# ComputeModule.net
KiCad netlist of a schematic drawn in Altium Designer
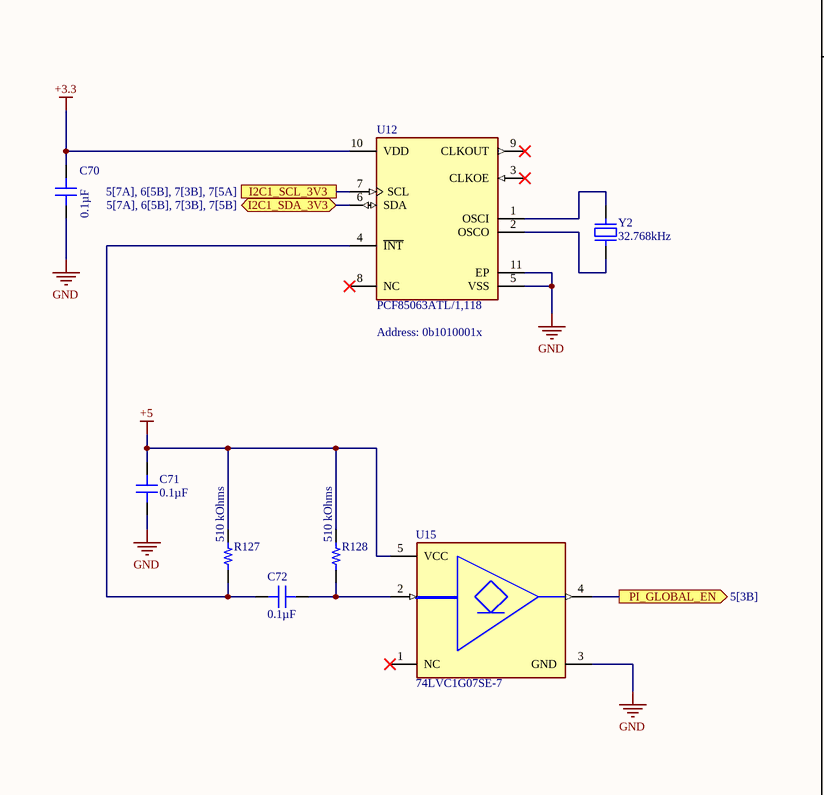
[diagram p0: ComputeModule.SchDoc, left]
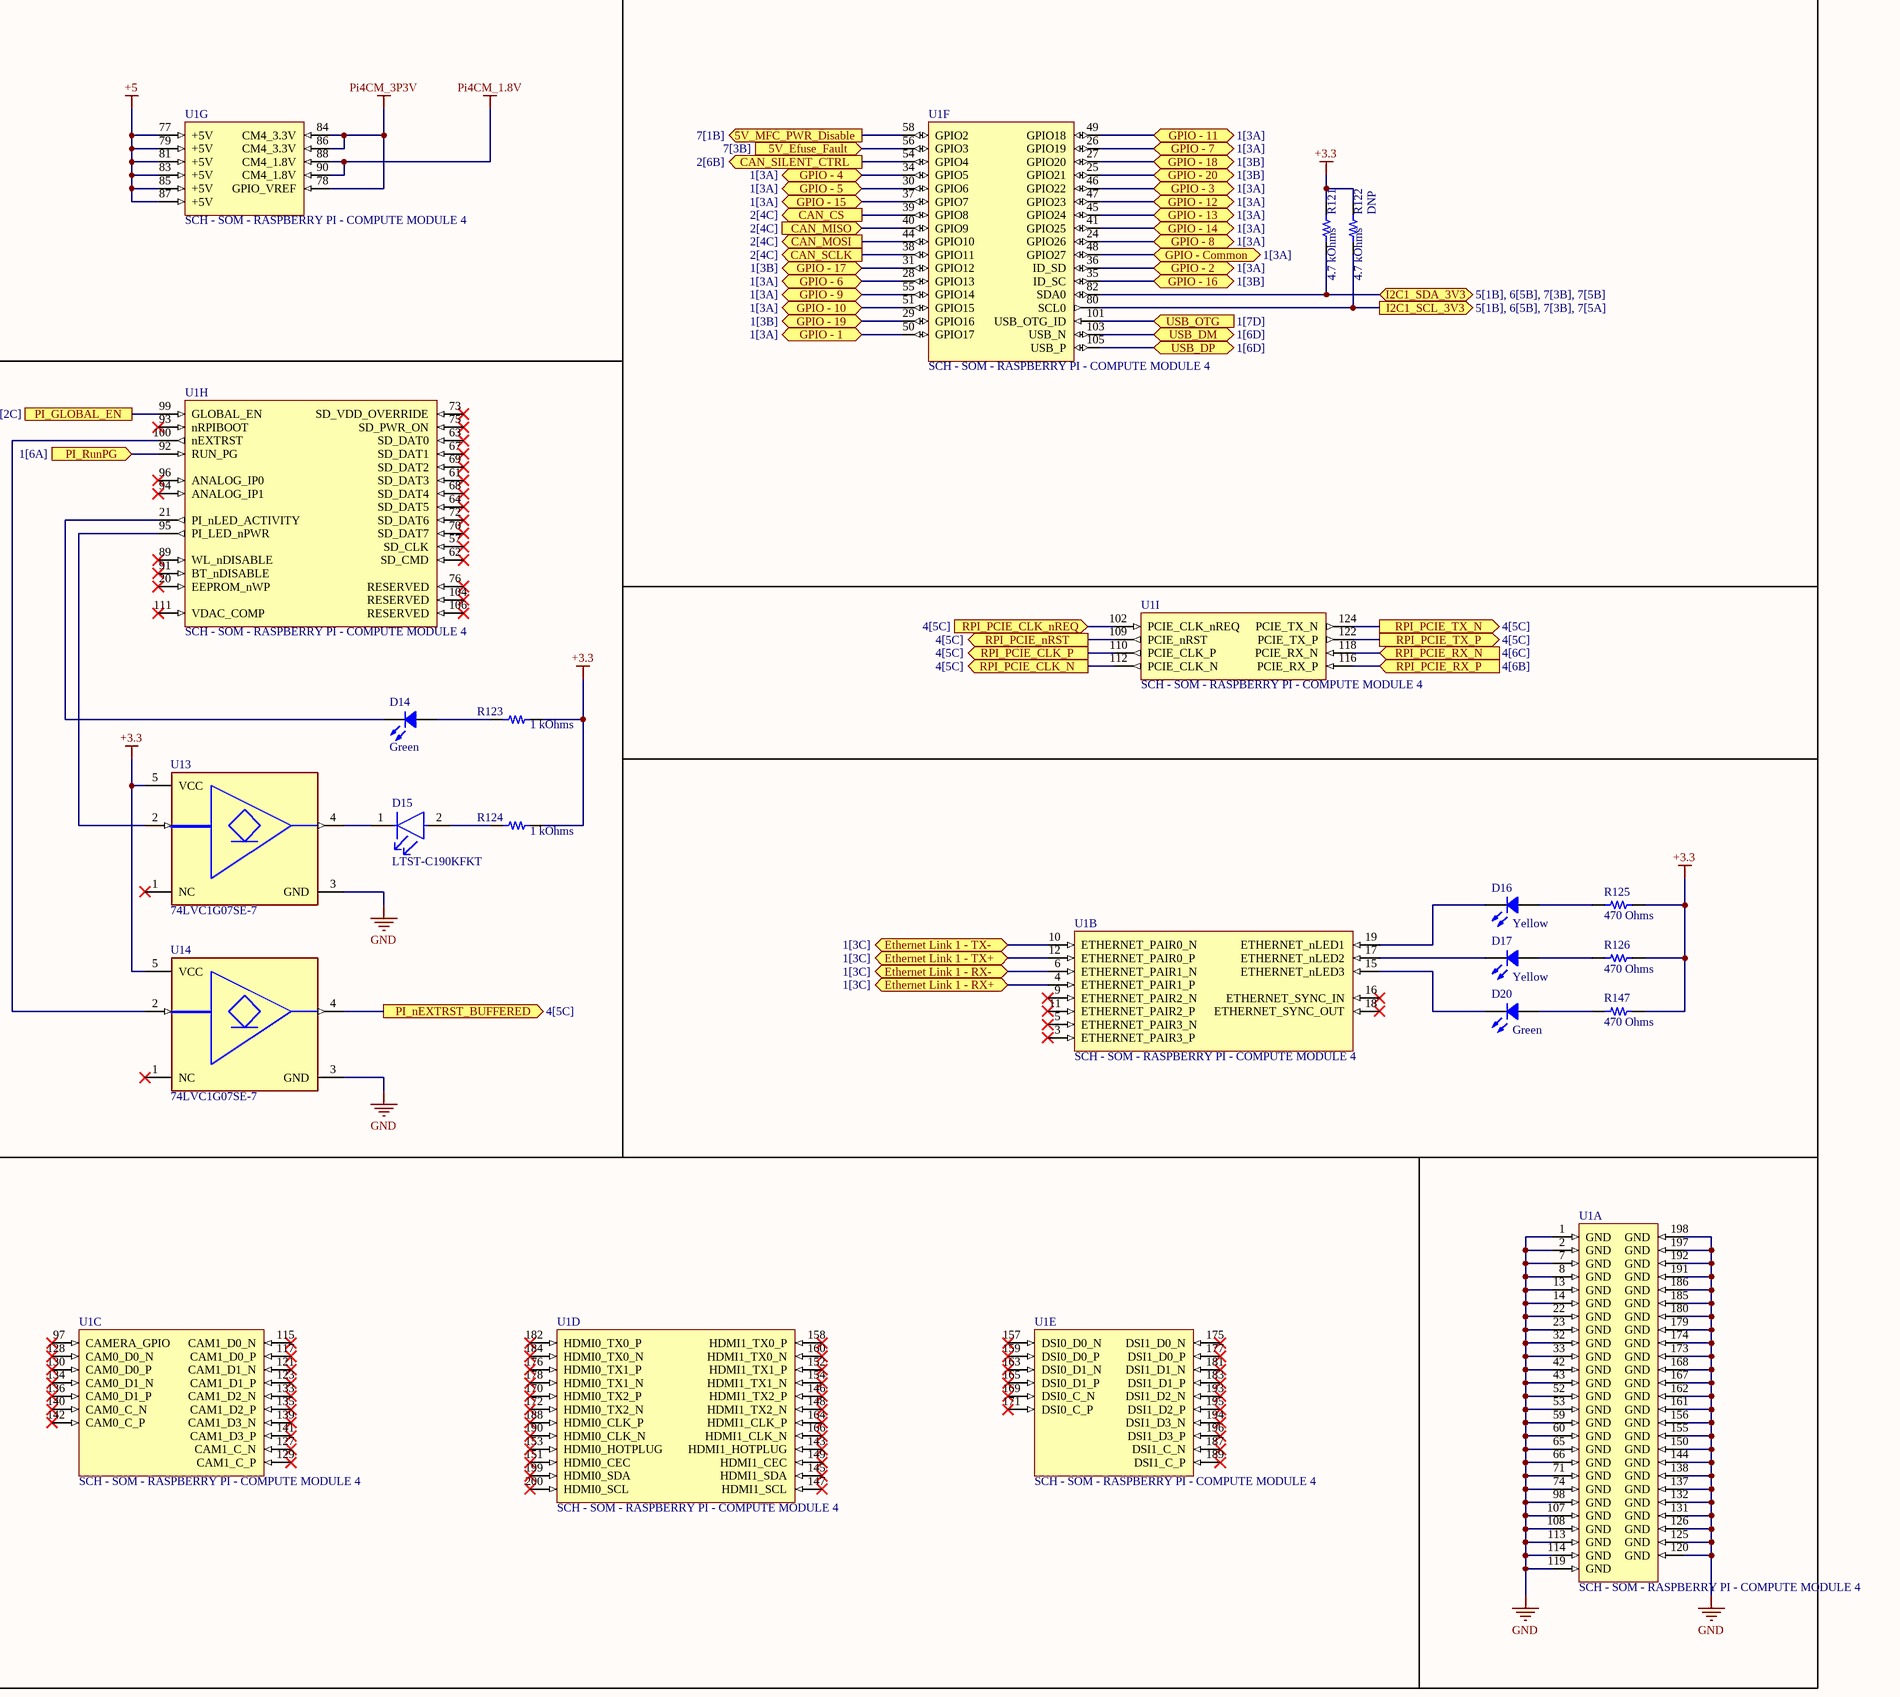
[diagram p1: ComputeModule.SchDoc, right]

(export (version "E")
  (design (tool "Eeschema 10.0.6"))
  (components
    (comp (ref "C70")
      (value "0.1µF")
      (footprint "CAP 0603_1608")
      (description "CAP CER 0.1UF 25V X7R 0603")
      (fields
        (field (name "PART NUMBER") "CL10B104KA8WPNC")
        (field (name "MANUFACTURER") "Samsung Electro-Mechanics")
      )
      (libsource (lib "Celestial Altium Library - altium_library") (part "Capacitor"))
    )
    (comp (ref "C71")
      (value "0.1µF")
      (footprint "CAP 0603_1608")
      (description "CAP CER 0.1UF 25V X7R 0603")
      (fields
        (field (name "PART NUMBER") "CL10B104KA8WPNC")
        (field (name "MANUFACTURER") "Samsung Electro-Mechanics")
      )
      (libsource (lib "Celestial Altium Library - altium_library") (part "Capacitor"))
    )
    (comp (ref "C72")
      (value "0.1µF")
      (footprint "CAP 0603_1608")
      (description "CAP CER 0.1UF 25V X7R 0603")
      (fields
        (field (name "PART NUMBER") "CL10B104KA8WPNC")
        (field (name "MANUFACTURER") "Samsung Electro-Mechanics")
      )
      (libsource (lib "Celestial Altium Library - altium_library") (part "Capacitor"))
    )
    (comp (ref "D14")
      (value "Green")
      (footprint "LED 0603_1608 GREEN")
      (description "LED GREEN CLEAR CHIP SMD")
      (fields (field (name "PART NUMBER") "LTST-C193KGKT-5A") (field (name "MANUFACTURER") "Lite-On Inc."))
      (libsource (lib "Celestial Altium Library - altium_library") (part "LED"))
    )
    (comp (ref "D15")
      (value "LTST-C190KFKT")
      (footprint "FP-LTST-C190KFKT-MFG")
      (description "LED ORANGE CLEAR CHIP SMD")
      (libsource (lib "Altium Content Vault") (part "8706943c75ba83719d021d2fdc84c58"))
    )
    (comp (ref "D16")
      (value "Yellow")
      (footprint "LED 0603_1608 YELLOW")
      (description "LED YELLOW CLEAR SMD")
      (fields (field (name "PART NUMBER") "LTST-C191KSKT") (field (name "MANUFACTURER") "Lite-On Inc."))
      (libsource (lib "Celestial Altium Library - altium_library") (part "LED"))
    )
    (comp (ref "D17")
      (value "Yellow")
      (footprint "LED 0603_1608 YELLOW")
      (description "LED YELLOW CLEAR SMD")
      (fields (field (name "PART NUMBER") "LTST-C191KSKT") (field (name "MANUFACTURER") "Lite-On Inc."))
      (libsource (lib "Celestial Altium Library - altium_library") (part "LED"))
    )
    (comp (ref "D20")
      (value "Green")
      (footprint "LED 0603_1608 GREEN")
      (description "LED GREEN CLEAR CHIP SMD")
      (fields (field (name "PART NUMBER") "LTST-C193KGKT-5A") (field (name "MANUFACTURER") "Lite-On Inc."))
      (libsource (lib "Celestial Altium Library - altium_library") (part "LED"))
    )
    (comp (ref "R121")
      (value "4.7 kOhms")
      (footprint "RES 0603_1608")
      (description "RES 4.7K OHM 1% 1/10W 0603")
      (fields
        (field (name "PART NUMBER") "RMCF0603FT4K70")
        (field (name "MANUFACTURER") "Stackpole Electronics Inc")
      )
      (libsource (lib "Celestial Altium Library - altium_library") (part "Resistor"))
    )
    (comp (ref "R122")
      (value "4.7 kOhms")
      (footprint "RES 0603_1608")
      (description "RES 4.7K OHM 1% 1/10W 0603")
      (fields
        (field (name "PART NUMBER") "RMCF0603FT4K70")
        (field (name "MANUFACTURER") "Stackpole Electronics Inc")
      )
      (libsource (lib "Celestial Altium Library - altium_library") (part "Resistor"))
    )
    (comp (ref "R123")
      (value "1 kOhms")
      (footprint "RES 0603_1608")
      (description "RES 1K OHM 1% 1/8W 0603")
      (fields
        (field (name "PART NUMBER") "RNCP0603FTD1K00")
        (field (name "MANUFACTURER") "Stackpole Electronics Inc")
      )
      (libsource (lib "Celestial Altium Library - altium_library") (part "Resistor"))
    )
    (comp (ref "R124")
      (value "1 kOhms")
      (footprint "RES 0603_1608")
      (description "RES 1K OHM 1% 1/8W 0603")
      (fields
        (field (name "PART NUMBER") "RNCP0603FTD1K00")
        (field (name "MANUFACTURER") "Stackpole Electronics Inc")
      )
      (libsource (lib "Celestial Altium Library - altium_library") (part "Resistor"))
    )
    (comp (ref "R125")
      (value "470 Ohms")
      (footprint "RES 0603_1608")
      (description "RES 470 OHM 5% 1/10W 0603")
      (fields
        (field (name "PART NUMBER") "RMCF0603JT470R")
        (field (name "MANUFACTURER") "Stackpole Electronics Inc")
      )
      (libsource (lib "Celestial Altium Library - altium_library") (part "Resistor"))
    )
    (comp (ref "R126")
      (value "470 Ohms")
      (footprint "RES 0603_1608")
      (description "RES 470 OHM 5% 1/10W 0603")
      (fields
        (field (name "PART NUMBER") "RMCF0603JT470R")
        (field (name "MANUFACTURER") "Stackpole Electronics Inc")
      )
      (libsource (lib "Celestial Altium Library - altium_library") (part "Resistor"))
    )
    (comp (ref "R127")
      (value "510 kOhms")
      (footprint "RES 0603_1608")
      (description "RES 510K OHM 5% 1/10W 0603")
      (fields
        (field (name "PART NUMBER") "RMCF0603JT510K")
        (field (name "MANUFACTURER") "Stackpole Electronics Inc")
      )
      (libsource (lib "Celestial Altium Library - altium_library") (part "Resistor"))
    )
    (comp (ref "R128")
      (value "510 kOhms")
      (footprint "RES 0603_1608")
      (description "RES 510K OHM 5% 1/10W 0603")
      (fields
        (field (name "PART NUMBER") "RMCF0603JT510K")
        (field (name "MANUFACTURER") "Stackpole Electronics Inc")
      )
      (libsource (lib "Celestial Altium Library - altium_library") (part "Resistor"))
    )
    (comp (ref "R147")
      (value "470 Ohms")
      (footprint "RES 0603_1608")
      (description "RES 470 OHM 5% 1/10W 0603")
      (fields
        (field (name "PART NUMBER") "RMCF0603JT470R")
        (field (name "MANUFACTURER") "Stackpole Electronics Inc")
      )
      (libsource (lib "Celestial Altium Library - altium_library") (part "Resistor"))
    )
    (comp (ref "U1")
      (value "SCH - SOM - RASPBERRY PI - COMPUTE MODULE 4")
      (footprint "PCB - SOM - Pi4 Compute Module")
      (libsource (lib "HAB_ICs") (part "SCH - SOM - RASPBERRY PI - COMPUTE MODULE 4"))
    )
    (comp (ref "U12")
      (value "PCF85063ATL/1,118")
      (footprint "FP-SOT1197-1-MFG")
      (description "IC RTC CLK/CALENDAR I2C 10-SON")
      (fields
        (field (name "OCTOPART") "https://octopart.com/pcf85063atl%2F1%2C118-nxp+semiconductors-27552710")
        (field (name "MANUFACTURER") "NXP Semiconductors")
      )
      (libsource (lib "Altium Content Vault") (part "f858fb8a8c6159aa53dbba272f77247"))
    )
    (comp (ref "U13")
      (value "74LVC1G07SE-7")
      (footprint "FP-SOT353-MFG")
      (description "IC BUF NON-INVERT 5.5V SOT353")
      (fields
        (field (name "MANUFACTURER") "Diodes Inc.")
        (field (name "OCTOPART") "https://octopart.com/74lvc1g07se-7-diodes+inc.-18882698")
      )
      (libsource (lib "Altium Content Vault") (part "1af1fa4339a335f25e71eb4dc151592"))
    )
    (comp (ref "U14")
      (value "74LVC1G07SE-7")
      (footprint "FP-SOT353-MFG")
      (description "IC BUF NON-INVERT 5.5V SOT353")
      (fields
        (field (name "MANUFACTURER") "Diodes Inc.")
        (field (name "OCTOPART") "https://octopart.com/74lvc1g07se-7-diodes+inc.-18882698")
      )
      (libsource (lib "Altium Content Vault") (part "1af1fa4339a335f25e71eb4dc151592"))
    )
    (comp (ref "U15")
      (value "74LVC1G07SE-7")
      (footprint "FP-SOT353-MFG")
      (description "IC BUF NON-INVERT 5.5V SOT353")
      (fields
        (field (name "MANUFACTURER") "Diodes Inc.")
        (field (name "OCTOPART") "https://octopart.com/74lvc1g07se-7-diodes+inc.-18882698")
      )
      (libsource (lib "Altium Content Vault") (part "1af1fa4339a335f25e71eb4dc151592"))
    )
    (comp (ref "Y2")
      (value "32.768kHz")
      (footprint "ABRACON ABS07")
      (description "IOT 32.786KHZ XTAL")
      (fields
        (field (name "PART NUMBER") "ABS07-166-32.768KHZ-T")
        (field (name "MANUFACTURER") "Abracon LLC")
      )
      (libsource (lib "Celestial Altium Library - altium_library") (part "Abracon Crystal ABS07"))
    )
  )
  (nets
    (net (code "1") (name "+3.3") (class "Default")
      (node (ref "C70") (pin "2") (pinfunction "2_2") (pintype "passive"))
      (node (ref "R121") (pin "2") (pinfunction "2_2") (pintype "passive"))
      (node (ref "R122") (pin "2") (pinfunction "2_2") (pintype "passive"))
      (node (ref "R123") (pin "1") (pinfunction "1_1") (pintype "passive"))
      (node (ref "R124") (pin "1") (pinfunction "1_1") (pintype "passive"))
      (node (ref "R125") (pin "2") (pinfunction "2_2") (pintype "passive"))
      (node (ref "R126") (pin "2") (pinfunction "2_2") (pintype "passive"))
      (node (ref "R147") (pin "2") (pinfunction "2_2") (pintype "passive"))
      (node (ref "U12") (pin "10") (pinfunction "VDD_10") (pintype "power_in"))
      (node (ref "U13") (pin "5") (pinfunction "VCC_5") (pintype "power_in"))
      (node (ref "U14") (pin "5") (pinfunction "VCC_5") (pintype "power_in"))
    )
    (net (code "2") (name "+5") (class "Default")
      (node (ref "C71") (pin "1") (pinfunction "1_1") (pintype "passive"))
      (node (ref "R127") (pin "2") (pinfunction "2_2") (pintype "passive"))
      (node (ref "R128") (pin "2") (pinfunction "2_2") (pintype "passive"))
      (node (ref "U1") (pin "77") (pinfunction "+5V_77") (pintype "input"))
      (node (ref "U1") (pin "79") (pinfunction "+5V_79") (pintype "input"))
      (node (ref "U1") (pin "81") (pinfunction "+5V_81") (pintype "input"))
      (node (ref "U1") (pin "83") (pinfunction "+5V_83") (pintype "input"))
      (node (ref "U1") (pin "85") (pinfunction "+5V_85") (pintype "input"))
      (node (ref "U1") (pin "87") (pinfunction "+5V_87") (pintype "input"))
      (node (ref "U15") (pin "5") (pinfunction "VCC_5") (pintype "power_in"))
    )
    (net (code "3") (name "/5V_Efuse_Fault") (class "Default")
      (node (ref "U1") (pin "56") (pinfunction "GPIO3_56") (pintype "bidirectional"))
    )
    (net (code "4") (name "/5V_MFC_PWR_Disable") (class "Default")
      (node (ref "U1") (pin "58") (pinfunction "GPIO2_58") (pintype "bidirectional"))
    )
    (net (code "5") (name "/CAN_CS") (class "Default")
      (node (ref "U1") (pin "39") (pinfunction "GPIO8_39") (pintype "bidirectional"))
    )
    (net (code "6") (name "/CAN_MISO") (class "Default")
      (node (ref "U1") (pin "40") (pinfunction "GPIO9_40") (pintype "bidirectional"))
    )
    (net (code "7") (name "/CAN_MOSI") (class "Default")
      (node (ref "U1") (pin "44") (pinfunction "GPIO10_44") (pintype "bidirectional"))
    )
    (net (code "8") (name "/CAN_SCLK") (class "Default")
      (node (ref "U1") (pin "38") (pinfunction "GPIO11_38") (pintype "bidirectional"))
    )
    (net (code "9") (name "/CAN_SILENT_CTRL") (class "Default")
      (node (ref "U1") (pin "54") (pinfunction "GPIO4_54") (pintype "bidirectional"))
    )
    (net (code "10") (name "/Ethernet Link 1 - RX+") (class "Default")
      (node (ref "U1") (pin "4") (pinfunction "ETHERNET_PAIR1_P_4") (pintype "input"))
    )
    (net (code "11") (name "/Ethernet Link 1 - RX-") (class "Default")
      (node (ref "U1") (pin "6") (pinfunction "ETHERNET_PAIR1_N_6") (pintype "input"))
    )
    (net (code "12") (name "/Ethernet Link 1 - TX+") (class "Default")
      (node (ref "U1") (pin "12") (pinfunction "ETHERNET_PAIR0_P_12") (pintype "input"))
    )
    (net (code "13") (name "/Ethernet Link 1 - TX-") (class "Default")
      (node (ref "U1") (pin "10") (pinfunction "ETHERNET_PAIR0_N_10") (pintype "input"))
    )
    (net (code "14") (name "/GPIO - 1") (class "Default")
      (node (ref "U1") (pin "50") (pinfunction "GPIO17_50") (pintype "bidirectional"))
    )
    (net (code "15") (name "/GPIO - 2") (class "Default")
      (node (ref "U1") (pin "36") (pinfunction "ID_SD_36") (pintype "bidirectional"))
    )
    (net (code "16") (name "/GPIO - 3") (class "Default")
      (node (ref "U1") (pin "46") (pinfunction "GPIO22_46") (pintype "bidirectional"))
    )
    (net (code "17") (name "/GPIO - 4") (class "Default")
      (node (ref "U1") (pin "34") (pinfunction "GPIO5_34") (pintype "bidirectional"))
    )
    (net (code "18") (name "/GPIO - 5") (class "Default")
      (node (ref "U1") (pin "30") (pinfunction "GPIO6_30") (pintype "bidirectional"))
    )
    (net (code "19") (name "/GPIO - 6") (class "Default")
      (node (ref "U1") (pin "28") (pinfunction "GPIO13_28") (pintype "bidirectional"))
    )
    (net (code "20") (name "/GPIO - 7") (class "Default")
      (node (ref "U1") (pin "26") (pinfunction "GPIO19_26") (pintype "bidirectional"))
    )
    (net (code "21") (name "/GPIO - 8") (class "Default")
      (node (ref "U1") (pin "24") (pinfunction "GPIO26_24") (pintype "bidirectional"))
    )
    (net (code "22") (name "/GPIO - 9") (class "Default")
      (node (ref "U1") (pin "55") (pinfunction "GPIO14_55") (pintype "bidirectional"))
    )
    (net (code "23") (name "/GPIO - 10") (class "Default")
      (node (ref "U1") (pin "51") (pinfunction "GPIO15_51") (pintype "bidirectional"))
    )
    (net (code "24") (name "/GPIO - 11") (class "Default")
      (node (ref "U1") (pin "49") (pinfunction "GPIO18_49") (pintype "bidirectional"))
    )
    (net (code "25") (name "/GPIO - 12") (class "Default")
      (node (ref "U1") (pin "47") (pinfunction "GPIO23_47") (pintype "bidirectional"))
    )
    (net (code "26") (name "/GPIO - 13") (class "Default")
      (node (ref "U1") (pin "45") (pinfunction "GPIO24_45") (pintype "bidirectional"))
    )
    (net (code "27") (name "/GPIO - 14") (class "Default")
      (node (ref "U1") (pin "41") (pinfunction "GPIO25_41") (pintype "bidirectional"))
    )
    (net (code "28") (name "/GPIO - 15") (class "Default")
      (node (ref "U1") (pin "37") (pinfunction "GPIO7_37") (pintype "bidirectional"))
    )
    (net (code "29") (name "/GPIO - 16") (class "Default")
      (node (ref "U1") (pin "35") (pinfunction "ID_SC_35") (pintype "bidirectional"))
    )
    (net (code "30") (name "/GPIO - 17") (class "Default")
      (node (ref "U1") (pin "31") (pinfunction "GPIO12_31") (pintype "bidirectional"))
    )
    (net (code "31") (name "/GPIO - 18") (class "Default")
      (node (ref "U1") (pin "27") (pinfunction "GPIO20_27") (pintype "bidirectional"))
    )
    (net (code "32") (name "/GPIO - 19") (class "Default")
      (node (ref "U1") (pin "29") (pinfunction "GPIO16_29") (pintype "bidirectional"))
    )
    (net (code "33") (name "/GPIO - 20") (class "Default")
      (node (ref "U1") (pin "25") (pinfunction "GPIO21_25") (pintype "bidirectional"))
    )
    (net (code "34") (name "/GPIO - Common") (class "Default")
      (node (ref "U1") (pin "48") (pinfunction "GPIO27_48") (pintype "bidirectional"))
    )
    (net (code "35") (name "/I2C1_SCL_3V3") (class "Default")
      (node (ref "R122") (pin "1") (pinfunction "1_1") (pintype "passive"))
      (node (ref "U1") (pin "80") (pinfunction "SCL0_80") (pintype "output"))
      (node (ref "U12") (pin "7") (pinfunction "SCL_7") (pintype "input"))
    )
    (net (code "36") (name "/I2C1_SDA_3V3") (class "Default")
      (node (ref "R121") (pin "1") (pinfunction "1_1") (pintype "passive"))
      (node (ref "U1") (pin "82") (pinfunction "SDA0_82") (pintype "bidirectional"))
      (node (ref "U12") (pin "6") (pinfunction "SDA_6") (pintype "bidirectional"))
    )
    (net (code "37") (name "/PI_GLOBAL_EN") (class "Default")
      (node (ref "U1") (pin "99") (pinfunction "GLOBAL_EN_99") (pintype "input"))
      (node (ref "U15") (pin "4") (pinfunction "Y_4") (pintype "output"))
    )
    (net (code "38") (name "/PI_RunPG") (class "Default")
      (node (ref "U1") (pin "92") (pinfunction "RUN_PG_92") (pintype "input"))
    )
    (net (code "39") (name "/PI_nEXTRST_BUFFERED") (class "Default")
      (node (ref "U14") (pin "4") (pinfunction "Y_4") (pintype "output"))
    )
    (net (code "40") (name "/RPI_PCIE_CLK_N") (class "Default")
      (node (ref "U1") (pin "112") (pinfunction "PCIE_CLK_N_112") (pintype "output"))
    )
    (net (code "41") (name "/RPI_PCIE_CLK_P") (class "Default")
      (node (ref "U1") (pin "110") (pinfunction "PCIE_CLK_P_110") (pintype "output"))
    )
    (net (code "42") (name "/RPI_PCIE_CLK_nREQ") (class "Default")
      (node (ref "U1") (pin "102") (pinfunction "PCIE_CLK_nREQ_102") (pintype "input"))
    )
    (net (code "43") (name "/RPI_PCIE_RX_N") (class "Default")
      (node (ref "U1") (pin "118") (pinfunction "PCIE_RX_N_118") (pintype "input"))
    )
    (net (code "44") (name "/RPI_PCIE_RX_P") (class "Default")
      (node (ref "U1") (pin "116") (pinfunction "PCIE_RX_P_116") (pintype "input"))
    )
    (net (code "45") (name "/RPI_PCIE_TX_N") (class "Default")
      (node (ref "U1") (pin "124") (pinfunction "PCIE_TX_N_124") (pintype "output"))
    )
    (net (code "46") (name "/RPI_PCIE_TX_P") (class "Default")
      (node (ref "U1") (pin "122") (pinfunction "PCIE_TX_P_122") (pintype "output"))
    )
    (net (code "47") (name "/RPI_PCIE_nRST") (class "Default")
      (node (ref "U1") (pin "109") (pinfunction "PCIE_nRST_109") (pintype "output"))
    )
    (net (code "48") (name "/USB_DM") (class "Default")
      (node (ref "U1") (pin "103") (pinfunction "USB_N_103") (pintype "bidirectional"))
    )
    (net (code "49") (name "/USB_DP") (class "Default")
      (node (ref "U1") (pin "105") (pinfunction "USB_P_105") (pintype "bidirectional"))
    )
    (net (code "50") (name "/USB_OTG") (class "Default")
      (node (ref "U1") (pin "101") (pinfunction "USB_OTG_ID_101") (pintype "input"))
    )
    (net (code "51") (name "GND") (class "Default")
      (node (ref "C70") (pin "1") (pinfunction "1_1") (pintype "passive"))
      (node (ref "C71") (pin "2") (pinfunction "2_2") (pintype "passive"))
      (node (ref "U1") (pin "1") (pinfunction "GND_1") (pintype "input"))
      (node (ref "U1") (pin "107") (pinfunction "GND_107") (pintype "input"))
      (node (ref "U1") (pin "108") (pinfunction "GND_108") (pintype "input"))
      (node (ref "U1") (pin "113") (pinfunction "GND_113") (pintype "input"))
      (node (ref "U1") (pin "114") (pinfunction "GND_114") (pintype "input"))
      (node (ref "U1") (pin "119") (pinfunction "GND_119") (pintype "input"))
      (node (ref "U1") (pin "120") (pinfunction "GND_120") (pintype "input"))
      (node (ref "U1") (pin "125") (pinfunction "GND_125") (pintype "input"))
      (node (ref "U1") (pin "126") (pinfunction "GND_126") (pintype "input"))
      (node (ref "U1") (pin "13") (pinfunction "GND_13") (pintype "input"))
      (node (ref "U1") (pin "131") (pinfunction "GND_131") (pintype "input"))
      (node (ref "U1") (pin "132") (pinfunction "GND_132") (pintype "input"))
      (node (ref "U1") (pin "137") (pinfunction "GND_137") (pintype "input"))
      (node (ref "U1") (pin "138") (pinfunction "GND_138") (pintype "input"))
      (node (ref "U1") (pin "14") (pinfunction "GND_14") (pintype "input"))
      (node (ref "U1") (pin "144") (pinfunction "GND_144") (pintype "input"))
      (node (ref "U1") (pin "150") (pinfunction "GND_150") (pintype "input"))
      (node (ref "U1") (pin "155") (pinfunction "GND_155") (pintype "input"))
      (node (ref "U1") (pin "156") (pinfunction "GND_156") (pintype "input"))
      (node (ref "U1") (pin "161") (pinfunction "GND_161") (pintype "input"))
      (node (ref "U1") (pin "162") (pinfunction "GND_162") (pintype "input"))
      (node (ref "U1") (pin "167") (pinfunction "GND_167") (pintype "input"))
      (node (ref "U1") (pin "168") (pinfunction "GND_168") (pintype "input"))
      (node (ref "U1") (pin "173") (pinfunction "GND_173") (pintype "input"))
      (node (ref "U1") (pin "174") (pinfunction "GND_174") (pintype "input"))
      (node (ref "U1") (pin "179") (pinfunction "GND_179") (pintype "input"))
      (node (ref "U1") (pin "180") (pinfunction "GND_180") (pintype "input"))
      (node (ref "U1") (pin "185") (pinfunction "GND_185") (pintype "input"))
      (node (ref "U1") (pin "186") (pinfunction "GND_186") (pintype "input"))
      (node (ref "U1") (pin "191") (pinfunction "GND_191") (pintype "input"))
      (node (ref "U1") (pin "192") (pinfunction "GND_192") (pintype "input"))
      (node (ref "U1") (pin "197") (pinfunction "GND_197") (pintype "input"))
      (node (ref "U1") (pin "198") (pinfunction "GND_198") (pintype "input"))
      (node (ref "U1") (pin "2") (pinfunction "GND_2") (pintype "input"))
      (node (ref "U1") (pin "22") (pinfunction "GND_22") (pintype "input"))
      (node (ref "U1") (pin "23") (pinfunction "GND_23") (pintype "input"))
      (node (ref "U1") (pin "32") (pinfunction "GND_32") (pintype "input"))
      (node (ref "U1") (pin "33") (pinfunction "GND_33") (pintype "input"))
      (node (ref "U1") (pin "42") (pinfunction "GND_42") (pintype "input"))
      (node (ref "U1") (pin "43") (pinfunction "GND_43") (pintype "input"))
      (node (ref "U1") (pin "52") (pinfunction "GND_52") (pintype "input"))
      (node (ref "U1") (pin "53") (pinfunction "GND_53") (pintype "input"))
      (node (ref "U1") (pin "59") (pinfunction "GND_59") (pintype "input"))
      (node (ref "U1") (pin "60") (pinfunction "GND_60") (pintype "input"))
      (node (ref "U1") (pin "65") (pinfunction "GND_65") (pintype "input"))
      (node (ref "U1") (pin "66") (pinfunction "GND_66") (pintype "input"))
      (node (ref "U1") (pin "7") (pinfunction "GND_7") (pintype "input"))
      (node (ref "U1") (pin "71") (pinfunction "GND_71") (pintype "input"))
      (node (ref "U1") (pin "74") (pinfunction "GND_74") (pintype "input"))
      (node (ref "U1") (pin "8") (pinfunction "GND_8") (pintype "input"))
      (node (ref "U1") (pin "98") (pinfunction "GND_98") (pintype "input"))
      (node (ref "U12") (pin "11") (pinfunction "EP_11") (pintype "power_in"))
      (node (ref "U12") (pin "5") (pinfunction "VSS_5") (pintype "power_in"))
      (node (ref "U13") (pin "3") (pinfunction "GND_3") (pintype "power_in"))
      (node (ref "U14") (pin "3") (pinfunction "GND_3") (pintype "power_in"))
      (node (ref "U15") (pin "3") (pinfunction "GND_3") (pintype "power_in"))
    )
    (net (code "52") (name "Net-(D14-Pad1)") (class "Default")
      (node (ref "D14") (pin "1") (pinfunction "1_1") (pintype "passive"))
      (node (ref "R123") (pin "2") (pinfunction "2_2") (pintype "passive"))
    )
    (net (code "53") (name "Net-(D15-A)") (class "Default")
      (node (ref "D15") (pin "2") (pinfunction "A_2") (pintype "passive"))
      (node (ref "R124") (pin "2") (pinfunction "2_2") (pintype "passive"))
    )
    (net (code "54") (name "Net-(D15-C)") (class "Default")
      (node (ref "D15") (pin "1") (pinfunction "C_1") (pintype "passive"))
      (node (ref "U13") (pin "4") (pinfunction "Y_4") (pintype "output"))
    )
    (net (code "55") (name "Net-(D16-Pad1)") (class "Default")
      (node (ref "D16") (pin "1") (pinfunction "1_1") (pintype "passive"))
      (node (ref "R125") (pin "1") (pinfunction "1_1") (pintype "passive"))
    )
    (net (code "56") (name "Net-(D17-Pad1)") (class "Default")
      (node (ref "D17") (pin "1") (pinfunction "1_1") (pintype "passive"))
      (node (ref "R126") (pin "1") (pinfunction "1_1") (pintype "passive"))
    )
    (net (code "57") (name "Net-(D20-Pad1)") (class "Default")
      (node (ref "D20") (pin "1") (pinfunction "1_1") (pintype "passive"))
      (node (ref "R147") (pin "1") (pinfunction "1_1") (pintype "passive"))
    )
    (net (code "58") (name "Net-(U1B-ETHERNET_nLED1)") (class "Default")
      (node (ref "D16") (pin "2") (pinfunction "2_2") (pintype "passive"))
      (node (ref "U1") (pin "19") (pinfunction "ETHERNET_nLED1_19") (pintype "input"))
    )
    (net (code "59") (name "Net-(U1B-ETHERNET_nLED2)") (class "Default")
      (node (ref "D17") (pin "2") (pinfunction "2_2") (pintype "passive"))
      (node (ref "U1") (pin "17") (pinfunction "ETHERNET_nLED2_17") (pintype "input"))
    )
    (net (code "60") (name "Net-(U1B-ETHERNET_nLED3)") (class "Default")
      (node (ref "D20") (pin "2") (pinfunction "2_2") (pintype "passive"))
      (node (ref "U1") (pin "15") (pinfunction "ETHERNET_nLED3_15") (pintype "input"))
    )
    (net (code "61") (name "Net-(U1H-PI_nLED_ACTIVITY)") (class "Default")
      (node (ref "D14") (pin "2") (pinfunction "2_2") (pintype "passive"))
      (node (ref "U1") (pin "21") (pinfunction "PI_nLED_ACTIVITY_21") (pintype "output"))
    )
    (net (code "62") (name "Net-(U12-OSCI)") (class "Default")
      (node (ref "U12") (pin "1") (pinfunction "OSCI_1") (pintype "passive"))
      (node (ref "Y2") (pin "2") (pinfunction "2_2") (pintype "passive"))
    )
    (net (code "63") (name "Net-(U12-OSCO)") (class "Default")
      (node (ref "U12") (pin "2") (pinfunction "OSCO_2") (pintype "passive"))
      (node (ref "Y2") (pin "1") (pinfunction "1_1") (pintype "passive"))
    )
    (net (code "64") (name "Net-(U12-~{INT})") (class "Default")
      (node (ref "C72") (pin "2") (pinfunction "2_2") (pintype "passive"))
      (node (ref "R127") (pin "1") (pinfunction "1_1") (pintype "passive"))
      (node (ref "U12") (pin "4") (pinfunction "~{INT}_4") (pintype "open_collector"))
    )
    (net (code "65") (name "Net-(U13-A)") (class "Default")
      (node (ref "U1") (pin "95") (pinfunction "PI_LED_nPWR_95") (pintype "output"))
      (node (ref "U13") (pin "2") (pinfunction "A_2") (pintype "input"))
    )
    (net (code "66") (name "Net-(U14-A)") (class "Default")
      (node (ref "U1") (pin "100") (pinfunction "nEXTRST_100") (pintype "output"))
      (node (ref "U14") (pin "2") (pinfunction "A_2") (pintype "input"))
    )
    (net (code "67") (name "Net-(U15-A)") (class "Default")
      (node (ref "C72") (pin "1") (pinfunction "1_1") (pintype "passive"))
      (node (ref "R128") (pin "1") (pinfunction "1_1") (pintype "passive"))
      (node (ref "U15") (pin "2") (pinfunction "A_2") (pintype "input"))
    )
    (net (code "68") (name "Pi4CM_1.8V") (class "Default")
      (node (ref "U1") (pin "88") (pinfunction "CM4_1.8V_88") (pintype "input"))
      (node (ref "U1") (pin "90") (pinfunction "CM4_1.8V_90") (pintype "input"))
    )
    (net (code "69") (name "Pi4CM_3P3V") (class "Default")
      (node (ref "U1") (pin "78") (pinfunction "GPIO_VREF_78") (pintype "input"))
      (node (ref "U1") (pin "84") (pinfunction "CM4_3.3V_84") (pintype "input"))
      (node (ref "U1") (pin "86") (pinfunction "CM4_3.3V_86") (pintype "input"))
    )
    (net (code "70") (name "unconnected-(U1B-ETHERNET_PAIR2_N-Pad9)") (class "Default")
      (node (ref "U1") (pin "9") (pinfunction "ETHERNET_PAIR2_N_9") (pintype "input+no_connect"))
    )
    (net (code "71") (name "unconnected-(U1B-ETHERNET_PAIR2_P-Pad11)") (class "Default")
      (node (ref "U1") (pin "11") (pinfunction "ETHERNET_PAIR2_P_11") (pintype "input+no_connect"))
    )
    (net (code "72") (name "unconnected-(U1B-ETHERNET_PAIR3_N-Pad5)") (class "Default")
      (node (ref "U1") (pin "5") (pinfunction "ETHERNET_PAIR3_N_5") (pintype "input+no_connect"))
    )
    (net (code "73") (name "unconnected-(U1B-ETHERNET_PAIR3_P-Pad3)") (class "Default")
      (node (ref "U1") (pin "3") (pinfunction "ETHERNET_PAIR3_P_3") (pintype "input+no_connect"))
    )
    (net (code "74") (name "unconnected-(U1B-ETHERNET_SYNC_IN-Pad16)") (class "Default")
      (node (ref "U1") (pin "16") (pinfunction "ETHERNET_SYNC_IN_16") (pintype "input+no_connect"))
    )
    (net (code "75") (name "unconnected-(U1B-ETHERNET_SYNC_OUT-Pad18)") (class "Default")
      (node (ref "U1") (pin "18") (pinfunction "ETHERNET_SYNC_OUT_18") (pintype "input+no_connect"))
    )
    (net (code "76") (name "unconnected-(U1C-CAM0_C_N-Pad140)") (class "Default")
      (node (ref "U1") (pin "140") (pinfunction "CAM0_C_N_140") (pintype "input+no_connect"))
    )
    (net (code "77") (name "unconnected-(U1C-CAM0_C_P-Pad142)") (class "Default")
      (node (ref "U1") (pin "142") (pinfunction "CAM0_C_P_142") (pintype "input+no_connect"))
    )
    (net (code "78") (name "unconnected-(U1C-CAM0_D0_N-Pad128)") (class "Default")
      (node (ref "U1") (pin "128") (pinfunction "CAM0_D0_N_128") (pintype "input+no_connect"))
    )
    (net (code "79") (name "unconnected-(U1C-CAM0_D0_P-Pad130)") (class "Default")
      (node (ref "U1") (pin "130") (pinfunction "CAM0_D0_P_130") (pintype "input+no_connect"))
    )
    (net (code "80") (name "unconnected-(U1C-CAM0_D1_N-Pad134)") (class "Default")
      (node (ref "U1") (pin "134") (pinfunction "CAM0_D1_N_134") (pintype "input+no_connect"))
    )
    (net (code "81") (name "unconnected-(U1C-CAM0_D1_P-Pad136)") (class "Default")
      (node (ref "U1") (pin "136") (pinfunction "CAM0_D1_P_136") (pintype "input+no_connect"))
    )
    (net (code "82") (name "unconnected-(U1C-CAM1_C_N-Pad127)") (class "Default")
      (node (ref "U1") (pin "127") (pinfunction "CAM1_C_N_127") (pintype "input+no_connect"))
    )
    (net (code "83") (name "unconnected-(U1C-CAM1_C_P-Pad129)") (class "Default")
      (node (ref "U1") (pin "129") (pinfunction "CAM1_C_P_129") (pintype "input+no_connect"))
    )
    (net (code "84") (name "unconnected-(U1C-CAM1_D0_N-Pad115)") (class "Default")
      (node (ref "U1") (pin "115") (pinfunction "CAM1_D0_N_115") (pintype "input+no_connect"))
    )
    (net (code "85") (name "unconnected-(U1C-CAM1_D0_P-Pad117)") (class "Default")
      (node (ref "U1") (pin "117") (pinfunction "CAM1_D0_P_117") (pintype "input+no_connect"))
    )
    (net (code "86") (name "unconnected-(U1C-CAM1_D1_N-Pad121)") (class "Default")
      (node (ref "U1") (pin "121") (pinfunction "CAM1_D1_N_121") (pintype "input+no_connect"))
    )
    (net (code "87") (name "unconnected-(U1C-CAM1_D1_P-Pad123)") (class "Default")
      (node (ref "U1") (pin "123") (pinfunction "CAM1_D1_P_123") (pintype "input+no_connect"))
    )
    (net (code "88") (name "unconnected-(U1C-CAM1_D2_N-Pad133)") (class "Default")
      (node (ref "U1") (pin "133") (pinfunction "CAM1_D2_N_133") (pintype "input+no_connect"))
    )
    (net (code "89") (name "unconnected-(U1C-CAM1_D2_P-Pad135)") (class "Default")
      (node (ref "U1") (pin "135") (pinfunction "CAM1_D2_P_135") (pintype "input+no_connect"))
    )
    (net (code "90") (name "unconnected-(U1C-CAM1_D3_N-Pad139)") (class "Default")
      (node (ref "U1") (pin "139") (pinfunction "CAM1_D3_N_139") (pintype "input+no_connect"))
    )
    (net (code "91") (name "unconnected-(U1C-CAM1_D3_P-Pad141)") (class "Default")
      (node (ref "U1") (pin "141") (pinfunction "CAM1_D3_P_141") (pintype "input+no_connect"))
    )
    (net (code "92") (name "unconnected-(U1C-CAMERA_GPIO-Pad97)") (class "Default")
      (node (ref "U1") (pin "97") (pinfunction "CAMERA_GPIO_97") (pintype "input+no_connect"))
    )
    (net (code "93") (name "unconnected-(U1D-HDMI0_CEC-Pad151)") (class "Default")
      (node (ref "U1") (pin "151") (pinfunction "HDMI0_CEC_151") (pintype "input+no_connect"))
    )
    (net (code "94") (name "unconnected-(U1D-HDMI0_CLK_N-Pad190)") (class "Default")
      (node (ref "U1") (pin "190") (pinfunction "HDMI0_CLK_N_190") (pintype "input+no_connect"))
    )
    (net (code "95") (name "unconnected-(U1D-HDMI0_CLK_P-Pad188)") (class "Default")
      (node (ref "U1") (pin "188") (pinfunction "HDMI0_CLK_P_188") (pintype "input+no_connect"))
    )
    (net (code "96") (name "unconnected-(U1D-HDMI0_HOTPLUG-Pad153)") (class "Default")
      (node (ref "U1") (pin "153") (pinfunction "HDMI0_HOTPLUG_153") (pintype "input+no_connect"))
    )
    (net (code "97") (name "unconnected-(U1D-HDMI0_SCL-Pad200)") (class "Default")
      (node (ref "U1") (pin "200") (pinfunction "HDMI0_SCL_200") (pintype "input+no_connect"))
    )
    (net (code "98") (name "unconnected-(U1D-HDMI0_SDA-Pad199)") (class "Default")
      (node (ref "U1") (pin "199") (pinfunction "HDMI0_SDA_199") (pintype "input+no_connect"))
    )
    (net (code "99") (name "unconnected-(U1D-HDMI0_TX0_N-Pad184)") (class "Default")
      (node (ref "U1") (pin "184") (pinfunction "HDMI0_TX0_N_184") (pintype "input+no_connect"))
    )
    (net (code "100") (name "unconnected-(U1D-HDMI0_TX0_P-Pad182)") (class "Default")
      (node (ref "U1") (pin "182") (pinfunction "HDMI0_TX0_P_182") (pintype "input+no_connect"))
    )
    (net (code "101") (name "unconnected-(U1D-HDMI0_TX1_N-Pad178)") (class "Default")
      (node (ref "U1") (pin "178") (pinfunction "HDMI0_TX1_N_178") (pintype "input+no_connect"))
    )
    (net (code "102") (name "unconnected-(U1D-HDMI0_TX1_P-Pad176)") (class "Default")
      (node (ref "U1") (pin "176") (pinfunction "HDMI0_TX1_P_176") (pintype "input+no_connect"))
    )
    (net (code "103") (name "unconnected-(U1D-HDMI0_TX2_N-Pad172)") (class "Default")
      (node (ref "U1") (pin "172") (pinfunction "HDMI0_TX2_N_172") (pintype "input+no_connect"))
    )
    (net (code "104") (name "unconnected-(U1D-HDMI0_TX2_P-Pad170)") (class "Default")
      (node (ref "U1") (pin "170") (pinfunction "HDMI0_TX2_P_170") (pintype "input+no_connect"))
    )
    (net (code "105") (name "unconnected-(U1D-HDMI1_CEC-Pad149)") (class "Default")
      (node (ref "U1") (pin "149") (pinfunction "HDMI1_CEC_149") (pintype "input+no_connect"))
    )
    (net (code "106") (name "unconnected-(U1D-HDMI1_CLK_N-Pad166)") (class "Default")
      (node (ref "U1") (pin "166") (pinfunction "HDMI1_CLK_N_166") (pintype "input+no_connect"))
    )
    (net (code "107") (name "unconnected-(U1D-HDMI1_CLK_P-Pad164)") (class "Default")
      (node (ref "U1") (pin "164") (pinfunction "HDMI1_CLK_P_164") (pintype "input+no_connect"))
    )
    (net (code "108") (name "unconnected-(U1D-HDMI1_HOTPLUG-Pad143)") (class "Default")
      (node (ref "U1") (pin "143") (pinfunction "HDMI1_HOTPLUG_143") (pintype "input+no_connect"))
    )
    (net (code "109") (name "unconnected-(U1D-HDMI1_SCL-Pad147)") (class "Default")
      (node (ref "U1") (pin "147") (pinfunction "HDMI1_SCL_147") (pintype "input+no_connect"))
    )
    (net (code "110") (name "unconnected-(U1D-HDMI1_SDA-Pad145)") (class "Default")
      (node (ref "U1") (pin "145") (pinfunction "HDMI1_SDA_145") (pintype "input+no_connect"))
    )
    (net (code "111") (name "unconnected-(U1D-HDMI1_TX0_N-Pad160)") (class "Default")
      (node (ref "U1") (pin "160") (pinfunction "HDMI1_TX0_N_160") (pintype "input+no_connect"))
    )
    (net (code "112") (name "unconnected-(U1D-HDMI1_TX0_P-Pad158)") (class "Default")
      (node (ref "U1") (pin "158") (pinfunction "HDMI1_TX0_P_158") (pintype "input+no_connect"))
    )
    (net (code "113") (name "unconnected-(U1D-HDMI1_TX1_N-Pad154)") (class "Default")
      (node (ref "U1") (pin "154") (pinfunction "HDMI1_TX1_N_154") (pintype "input+no_connect"))
    )
    (net (code "114") (name "unconnected-(U1D-HDMI1_TX1_P-Pad152)") (class "Default")
      (node (ref "U1") (pin "152") (pinfunction "HDMI1_TX1_P_152") (pintype "input+no_connect"))
    )
    (net (code "115") (name "unconnected-(U1D-HDMI1_TX2_N-Pad148)") (class "Default")
      (node (ref "U1") (pin "148") (pinfunction "HDMI1_TX2_N_148") (pintype "input+no_connect"))
    )
    (net (code "116") (name "unconnected-(U1D-HDMI1_TX2_P-Pad146)") (class "Default")
      (node (ref "U1") (pin "146") (pinfunction "HDMI1_TX2_P_146") (pintype "input+no_connect"))
    )
    (net (code "117") (name "unconnected-(U1E-DSI0_C_N-Pad169)") (class "Default")
      (node (ref "U1") (pin "169") (pinfunction "DSI0_C_N_169") (pintype "input+no_connect"))
    )
    (net (code "118") (name "unconnected-(U1E-DSI0_C_P-Pad171)") (class "Default")
      (node (ref "U1") (pin "171") (pinfunction "DSI0_C_P_171") (pintype "input+no_connect"))
    )
    (net (code "119") (name "unconnected-(U1E-DSI0_D0_N-Pad157)") (class "Default")
      (node (ref "U1") (pin "157") (pinfunction "DSI0_D0_N_157") (pintype "input+no_connect"))
    )
    (net (code "120") (name "unconnected-(U1E-DSI0_D0_P-Pad159)") (class "Default")
      (node (ref "U1") (pin "159") (pinfunction "DSI0_D0_P_159") (pintype "input+no_connect"))
    )
    (net (code "121") (name "unconnected-(U1E-DSI0_D1_N-Pad163)") (class "Default")
      (node (ref "U1") (pin "163") (pinfunction "DSI0_D1_N_163") (pintype "input+no_connect"))
    )
    (net (code "122") (name "unconnected-(U1E-DSI0_D1_P-Pad165)") (class "Default")
      (node (ref "U1") (pin "165") (pinfunction "DSI0_D1_P_165") (pintype "input+no_connect"))
    )
    (net (code "123") (name "unconnected-(U1E-DSI1_C_N-Pad187)") (class "Default")
      (node (ref "U1") (pin "187") (pinfunction "DSI1_C_N_187") (pintype "input+no_connect"))
    )
    (net (code "124") (name "unconnected-(U1E-DSI1_C_P-Pad189)") (class "Default")
      (node (ref "U1") (pin "189") (pinfunction "DSI1_C_P_189") (pintype "input+no_connect"))
    )
    (net (code "125") (name "unconnected-(U1E-DSI1_D0_N-Pad175)") (class "Default")
      (node (ref "U1") (pin "175") (pinfunction "DSI1_D0_N_175") (pintype "input+no_connect"))
    )
    (net (code "126") (name "unconnected-(U1E-DSI1_D0_P-Pad177)") (class "Default")
      (node (ref "U1") (pin "177") (pinfunction "DSI1_D0_P_177") (pintype "input+no_connect"))
    )
    (net (code "127") (name "unconnected-(U1E-DSI1_D1_N-Pad181)") (class "Default")
      (node (ref "U1") (pin "181") (pinfunction "DSI1_D1_N_181") (pintype "input+no_connect"))
    )
    (net (code "128") (name "unconnected-(U1E-DSI1_D1_P-Pad183)") (class "Default")
      (node (ref "U1") (pin "183") (pinfunction "DSI1_D1_P_183") (pintype "input+no_connect"))
    )
    (net (code "129") (name "unconnected-(U1E-DSI1_D2_N-Pad193)") (class "Default")
      (node (ref "U1") (pin "193") (pinfunction "DSI1_D2_N_193") (pintype "input+no_connect"))
    )
    (net (code "130") (name "unconnected-(U1E-DSI1_D2_P-Pad195)") (class "Default")
      (node (ref "U1") (pin "195") (pinfunction "DSI1_D2_P_195") (pintype "input+no_connect"))
    )
    (net (code "131") (name "unconnected-(U1E-DSI1_D3_N-Pad194)") (class "Default")
      (node (ref "U1") (pin "194") (pinfunction "DSI1_D3_N_194") (pintype "input+no_connect"))
    )
    (net (code "132") (name "unconnected-(U1E-DSI1_D3_P-Pad196)") (class "Default")
      (node (ref "U1") (pin "196") (pinfunction "DSI1_D3_P_196") (pintype "input+no_connect"))
    )
    (net (code "133") (name "unconnected-(U1H-ANALOG_IP0-Pad96)") (class "Default")
      (node (ref "U1") (pin "96") (pinfunction "ANALOG_IP0_96") (pintype "input+no_connect"))
    )
    (net (code "134") (name "unconnected-(U1H-ANALOG_IP1-Pad94)") (class "Default")
      (node (ref "U1") (pin "94") (pinfunction "ANALOG_IP1_94") (pintype "input+no_connect"))
    )
    (net (code "135") (name "unconnected-(U1H-BT_nDISABLE-Pad91)") (class "Default")
      (node (ref "U1") (pin "91") (pinfunction "BT_nDISABLE_91") (pintype "input+no_connect"))
    )
    (net (code "136") (name "unconnected-(U1H-EEPROM_nWP-Pad20)") (class "Default")
      (node (ref "U1") (pin "20") (pinfunction "EEPROM_nWP_20") (pintype "input+no_connect"))
    )
    (net (code "137") (name "unconnected-(U1H-RESERVED-Pad76)") (class "Default")
      (node (ref "U1") (pin "76") (pinfunction "RESERVED_76") (pintype "input+no_connect"))
    )
    (net (code "138") (name "unconnected-(U1H-RESERVED-Pad104)") (class "Default")
      (node (ref "U1") (pin "104") (pinfunction "RESERVED_104") (pintype "input+no_connect"))
    )
    (net (code "139") (name "unconnected-(U1H-RESERVED-Pad106)") (class "Default")
      (node (ref "U1") (pin "106") (pinfunction "RESERVED_106") (pintype "input+no_connect"))
    )
    (net (code "140") (name "unconnected-(U1H-SD_CLK-Pad57)") (class "Default")
      (node (ref "U1") (pin "57") (pinfunction "SD_CLK_57") (pintype "input+no_connect"))
    )
    (net (code "141") (name "unconnected-(U1H-SD_CMD-Pad62)") (class "Default")
      (node (ref "U1") (pin "62") (pinfunction "SD_CMD_62") (pintype "input+no_connect"))
    )
    (net (code "142") (name "unconnected-(U1H-SD_DAT0-Pad63)") (class "Default")
      (node (ref "U1") (pin "63") (pinfunction "SD_DAT0_63") (pintype "input+no_connect"))
    )
    (net (code "143") (name "unconnected-(U1H-SD_DAT1-Pad67)") (class "Default")
      (node (ref "U1") (pin "67") (pinfunction "SD_DAT1_67") (pintype "input+no_connect"))
    )
    (net (code "144") (name "unconnected-(U1H-SD_DAT2-Pad69)") (class "Default")
      (node (ref "U1") (pin "69") (pinfunction "SD_DAT2_69") (pintype "input+no_connect"))
    )
    (net (code "145") (name "unconnected-(U1H-SD_DAT3-Pad61)") (class "Default")
      (node (ref "U1") (pin "61") (pinfunction "SD_DAT3_61") (pintype "input+no_connect"))
    )
    (net (code "146") (name "unconnected-(U1H-SD_DAT4-Pad68)") (class "Default")
      (node (ref "U1") (pin "68") (pinfunction "SD_DAT4_68") (pintype "input+no_connect"))
    )
    (net (code "147") (name "unconnected-(U1H-SD_DAT5-Pad64)") (class "Default")
      (node (ref "U1") (pin "64") (pinfunction "SD_DAT5_64") (pintype "input+no_connect"))
    )
    (net (code "148") (name "unconnected-(U1H-SD_DAT6-Pad72)") (class "Default")
      (node (ref "U1") (pin "72") (pinfunction "SD_DAT6_72") (pintype "input+no_connect"))
    )
    (net (code "149") (name "unconnected-(U1H-SD_DAT7-Pad70)") (class "Default")
      (node (ref "U1") (pin "70") (pinfunction "SD_DAT7_70") (pintype "input+no_connect"))
    )
    (net (code "150") (name "unconnected-(U1H-SD_PWR_ON-Pad75)") (class "Default")
      (node (ref "U1") (pin "75") (pinfunction "SD_PWR_ON_75") (pintype "input+no_connect"))
    )
    (net (code "151") (name "unconnected-(U1H-SD_VDD_OVERRIDE-Pad73)") (class "Default")
      (node (ref "U1") (pin "73") (pinfunction "SD_VDD_OVERRIDE_73") (pintype "input+no_connect"))
    )
    (net (code "152") (name "unconnected-(U1H-VDAC_COMP-Pad111)") (class "Default")
      (node (ref "U1") (pin "111") (pinfunction "VDAC_COMP_111") (pintype "input+no_connect"))
    )
    (net (code "153") (name "unconnected-(U1H-WL_nDISABLE-Pad89)") (class "Default")
      (node (ref "U1") (pin "89") (pinfunction "WL_nDISABLE_89") (pintype "input+no_connect"))
    )
    (net (code "154") (name "unconnected-(U1H-nRPIBOOT-Pad93)") (class "Default")
      (node (ref "U1") (pin "93") (pinfunction "nRPIBOOT_93") (pintype "input+no_connect"))
    )
    (net (code "155") (name "unconnected-(U12-CLKOE-Pad3)") (class "Default")
      (node (ref "U12") (pin "3") (pinfunction "CLKOE_3") (pintype "input+no_connect"))
    )
    (net (code "156") (name "unconnected-(U12-CLKOUT-Pad9)") (class "Default")
      (node (ref "U12") (pin "9") (pinfunction "CLKOUT_9") (pintype "output+no_connect"))
    )
    (net (code "157") (name "unconnected-(U12-NC-Pad8)") (class "Default")
      (node (ref "U12") (pin "8") (pinfunction "NC_8") (pintype "passive+no_connect"))
    )
    (net (code "158") (name "unconnected-(U13-NC-Pad1)") (class "Default")
      (node (ref "U13") (pin "1") (pinfunction "NC_1") (pintype "passive+no_connect"))
    )
    (net (code "159") (name "unconnected-(U14-NC-Pad1)") (class "Default")
      (node (ref "U14") (pin "1") (pinfunction "NC_1") (pintype "passive+no_connect"))
    )
    (net (code "160") (name "unconnected-(U15-NC-Pad1)") (class "Default")
      (node (ref "U15") (pin "1") (pinfunction "NC_1") (pintype "passive+no_connect"))
    )
  )
)
